# ProProject_dc_to_dc_2024-05-25.net
KiCad netlist of a schematic drawn in EasyEDA Pro
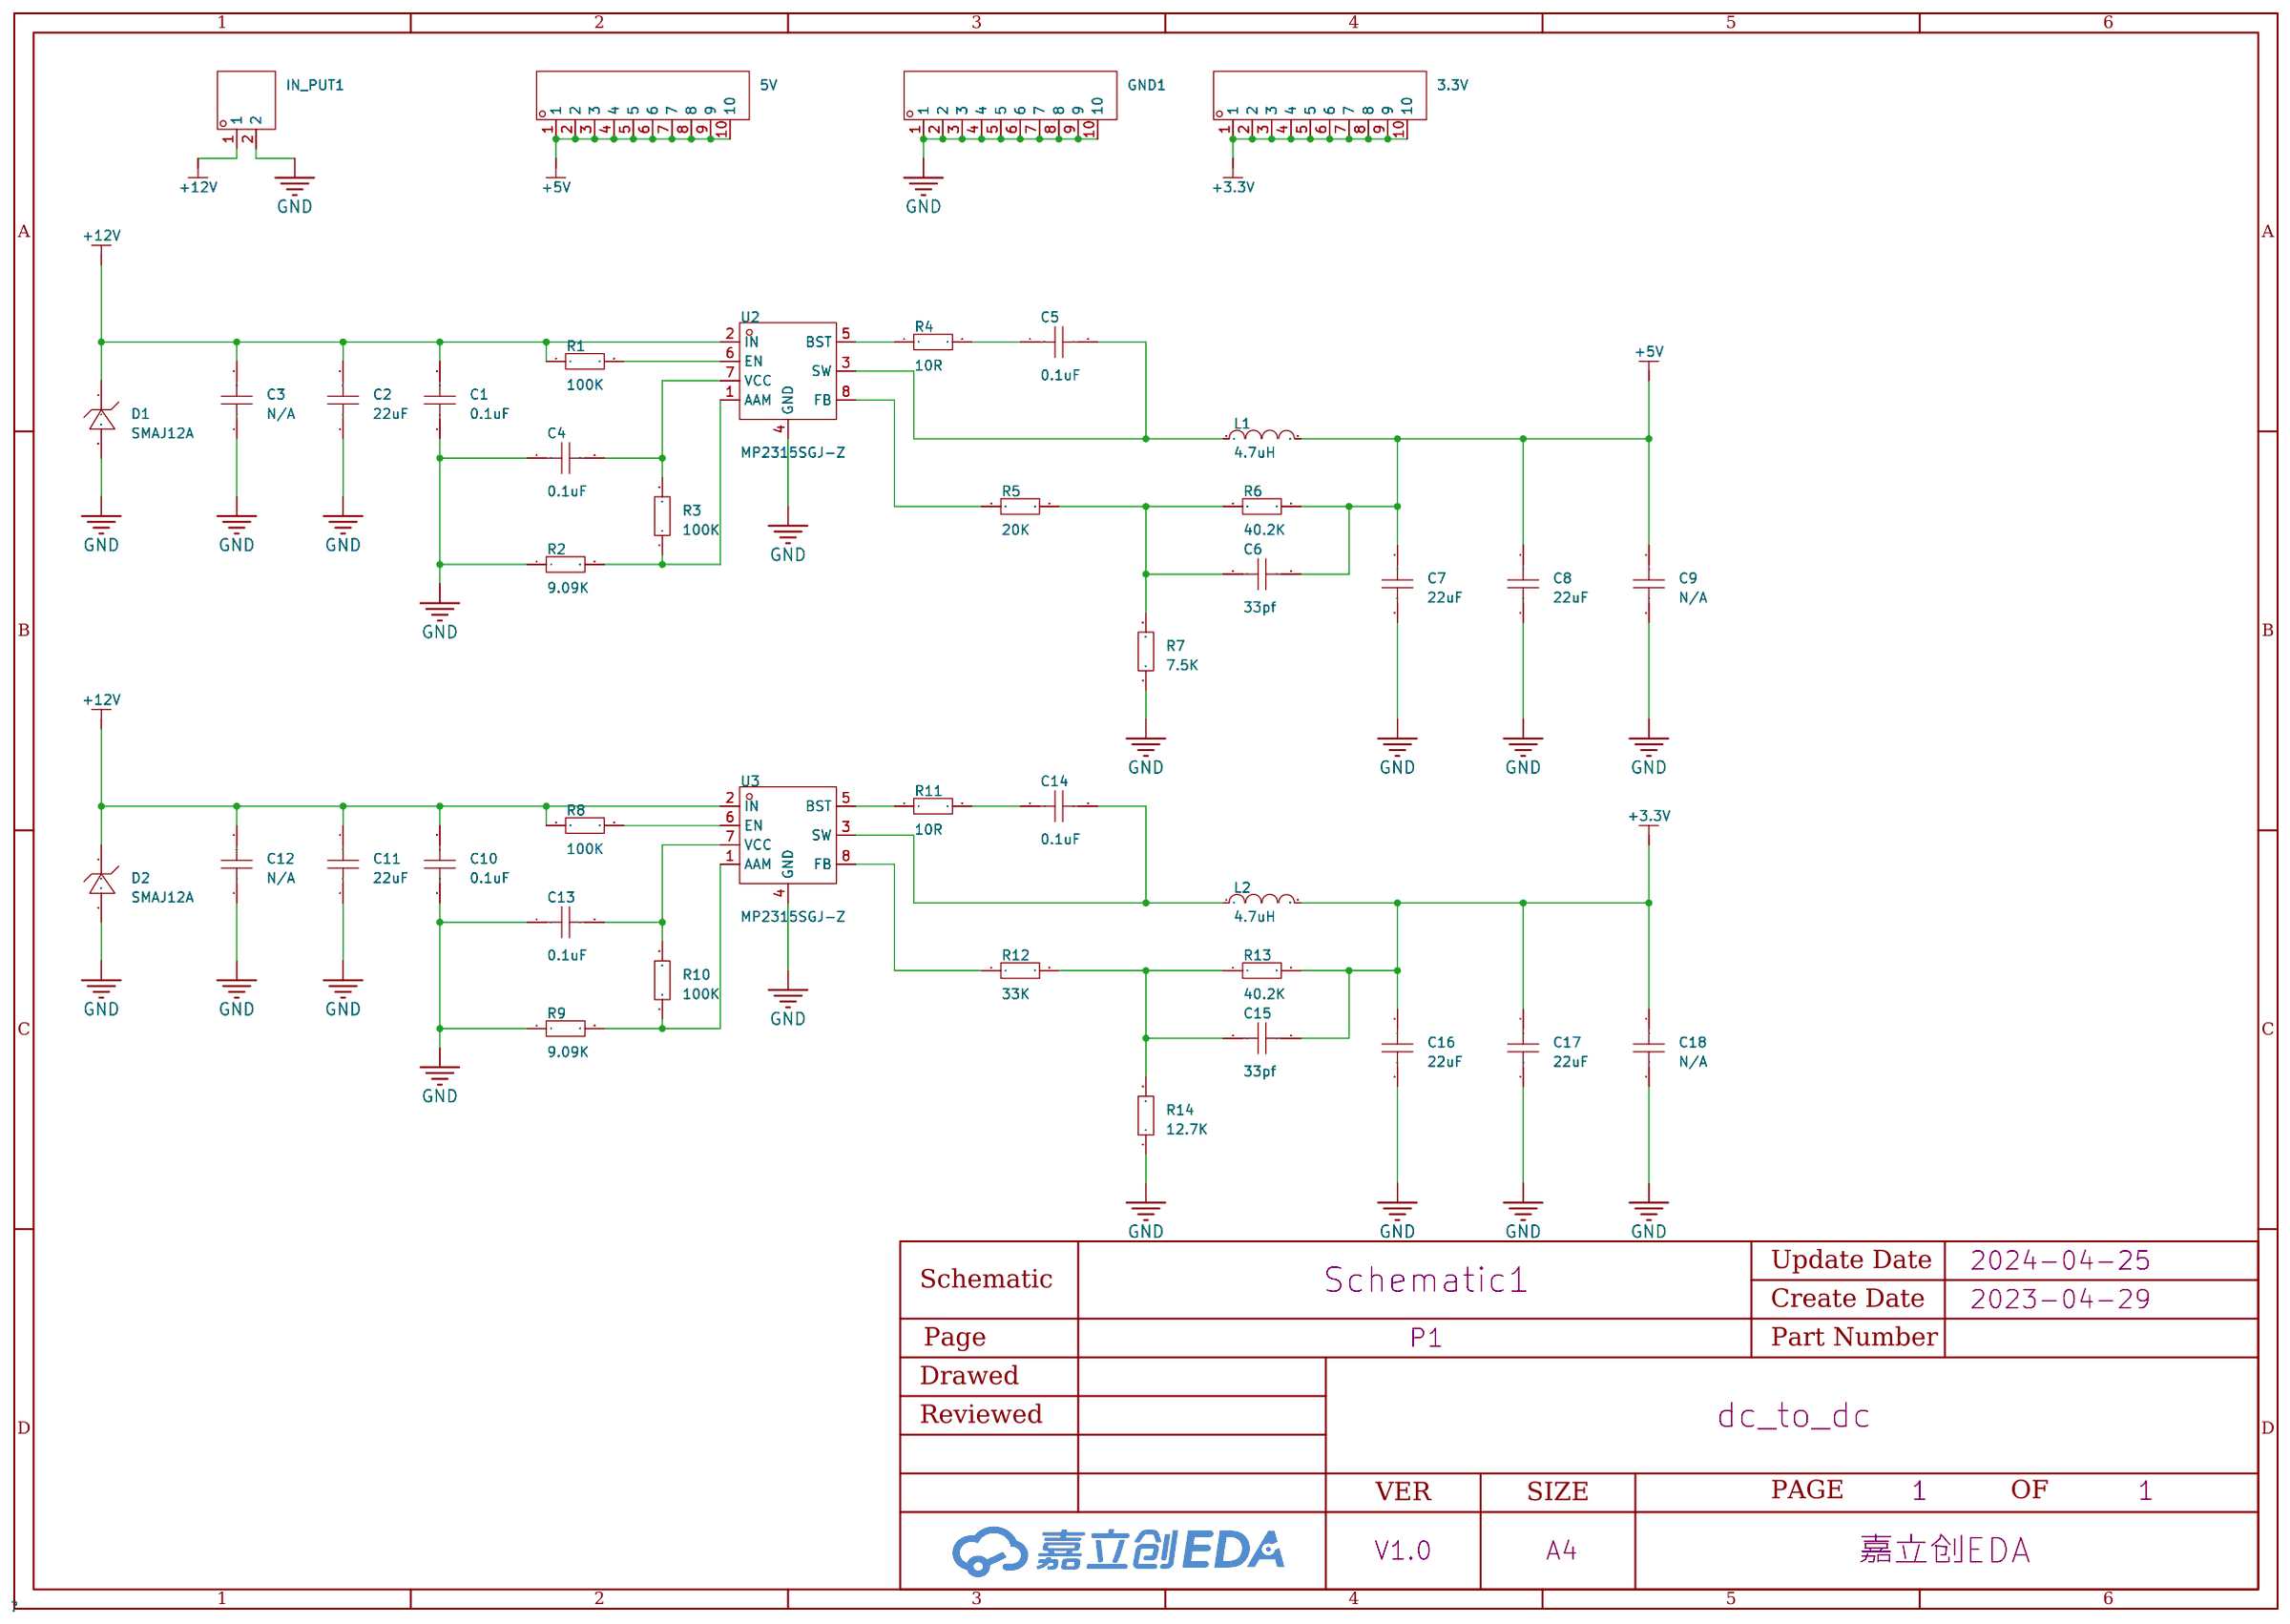
[diagram p0: schematic sheet]

(export (version "E")
  (design (tool "Eeschema 10.0.6"))
  (components
    (comp (ref "3.3V")
      (value "~")
      (footprint "easyedapro:HDR-TH_10P-P2.54-V-M-1")
      (libsource (lib "easyedapro") (part "Header-Male-2.54_1x10"))
    )
    (comp (ref "5V")
      (value "~")
      (footprint "easyedapro:HDR-TH_10P-P2.54-V-M-1")
      (libsource (lib "easyedapro") (part "Header-Male-2.54_1x10"))
    )
    (comp (ref "C1")
      (value "0.1uF")
      (footprint "easyedapro:C0603")
      (libsource (lib "easyedapro") (part "CapAcitance"))
    )
    (comp (ref "C2")
      (value "22uF")
      (footprint "easyedapro:C0603")
      (libsource (lib "easyedapro") (part "CapAcitance"))
    )
    (comp (ref "C3")
      (value "N/A")
      (footprint "easyedapro:C0603")
      (libsource (lib "easyedapro") (part "CapAcitance"))
    )
    (comp (ref "C4")
      (value "0.1uF")
      (footprint "easyedapro:C0603")
      (libsource (lib "easyedapro") (part "CapAcitance"))
    )
    (comp (ref "C5")
      (value "0.1uF")
      (footprint "easyedapro:C0603")
      (libsource (lib "easyedapro") (part "CapAcitance"))
    )
    (comp (ref "C6")
      (value "33pf")
      (footprint "easyedapro:C0603")
      (libsource (lib "easyedapro") (part "CapAcitance"))
    )
    (comp (ref "C7")
      (value "22uF")
      (footprint "easyedapro:C0603")
      (libsource (lib "easyedapro") (part "CapAcitance"))
    )
    (comp (ref "C8")
      (value "22uF")
      (footprint "easyedapro:C0603")
      (libsource (lib "easyedapro") (part "CapAcitance"))
    )
    (comp (ref "C9")
      (value "N/A")
      (footprint "easyedapro:C0603")
      (libsource (lib "easyedapro") (part "CapAcitance"))
    )
    (comp (ref "C10")
      (value "0.1uF")
      (footprint "easyedapro:C0603")
      (libsource (lib "easyedapro") (part "CapAcitance"))
    )
    (comp (ref "C11")
      (value "22uF")
      (footprint "easyedapro:C0603")
      (libsource (lib "easyedapro") (part "CapAcitance"))
    )
    (comp (ref "C12")
      (value "N/A")
      (footprint "easyedapro:C0603")
      (libsource (lib "easyedapro") (part "CapAcitance"))
    )
    (comp (ref "C13")
      (value "0.1uF")
      (footprint "easyedapro:C0603")
      (libsource (lib "easyedapro") (part "CapAcitance"))
    )
    (comp (ref "C14")
      (value "0.1uF")
      (footprint "easyedapro:C0603")
      (libsource (lib "easyedapro") (part "CapAcitance"))
    )
    (comp (ref "C15")
      (value "33pf")
      (footprint "easyedapro:C0603")
      (libsource (lib "easyedapro") (part "CapAcitance"))
    )
    (comp (ref "C16")
      (value "22uF")
      (footprint "easyedapro:C0603")
      (libsource (lib "easyedapro") (part "CapAcitance"))
    )
    (comp (ref "C17")
      (value "22uF")
      (footprint "easyedapro:C0603")
      (libsource (lib "easyedapro") (part "CapAcitance"))
    )
    (comp (ref "C18")
      (value "N/A")
      (footprint "easyedapro:C0603")
      (libsource (lib "easyedapro") (part "CapAcitance"))
    )
    (comp (ref "D1")
      (value "SMAJ12A")
      (footprint "easyedapro:SMA_L4.4-W2.8-LS5.4-RD")
      (description "极性:Unidirectional;峰值脉冲电流（10/1000us）:20.1A;箝位电压:19.9V;击穿电压（最小值）:13.3V;反向关断电压（典型值）:12V;")
      (libsource (lib "easyedapro") (part "SMAJ12A_C220440"))
    )
    (comp (ref "D2")
      (value "SMAJ12A")
      (footprint "easyedapro:SMA_L4.4-W2.8-LS5.4-RD")
      (description "极性:Unidirectional;峰值脉冲电流（10/1000us）:20.1A;箝位电压:19.9V;击穿电压（最小值）:13.3V;反向关断电压（典型值）:12V;")
      (libsource (lib "easyedapro") (part "SMAJ12A_C220440"))
    )
    (comp (ref "GND1")
      (value "~")
      (footprint "easyedapro:HDR-TH_10P-P2.54-V-M-1")
      (libsource (lib "easyedapro") (part "Header-Male-2.54_1x10"))
    )
    (comp (ref "IN_PUT1")
      (value "~")
      (footprint "easyedapro:HDR-TH_2P-P2.54-V-M-1")
      (libsource (lib "easyedapro") (part "210S-1*2P L=11.6MMGold-plated black"))
    )
    (comp (ref "L1")
      (value "4.7uH")
      (footprint "easyedapro:IND-SMD_L7.3-W6.6_MHCI06030")
      (description "电感值:4.7uH;精度:±20%;额定电流:5.5A;饱和电流(Isat):9A;")
      (fields
        (field (name "Manufacturer Part") "MHCI06030-4R7M-R8")
        (field (name "Manufacturer") "chilisin(奇力新)")
      )
      (libsource (lib "easyedapro") (part "MHCI06030-4R7M-R8"))
    )
    (comp (ref "L2")
      (value "4.7uH")
      (footprint "easyedapro:IND-SMD_L7.3-W6.6_MHCI06030")
      (description "电感值:4.7uH;精度:±20%;额定电流:5.5A;饱和电流(Isat):9A;")
      (fields
        (field (name "Manufacturer Part") "MHCI06030-4R7M-R8")
        (field (name "Manufacturer") "chilisin(奇力新)")
      )
      (libsource (lib "easyedapro") (part "MHCI06030-4R7M-R8"))
    )
    (comp (ref "R1") (value "100K") (footprint "easyedapro:R0603") (libsource (lib "easyedapro") (part "电阻")))
    (comp (ref "R2")
      (value "9.09K")
      (footprint "easyedapro:R0603")
      (libsource (lib "easyedapro") (part "电阻"))
    )
    (comp (ref "R3") (value "100K") (footprint "easyedapro:R0603") (libsource (lib "easyedapro") (part "电阻")))
    (comp (ref "R4") (value "10R") (footprint "easyedapro:R0603") (libsource (lib "easyedapro") (part "电阻")))
    (comp (ref "R5") (value "20K") (footprint "easyedapro:R0603") (libsource (lib "easyedapro") (part "电阻")))
    (comp (ref "R6")
      (value "40.2K")
      (footprint "easyedapro:R0603")
      (libsource (lib "easyedapro") (part "电阻"))
    )
    (comp (ref "R7") (value "7.5K") (footprint "easyedapro:R0603") (libsource (lib "easyedapro") (part "电阻")))
    (comp (ref "R8") (value "100K") (footprint "easyedapro:R0603") (libsource (lib "easyedapro") (part "电阻")))
    (comp (ref "R9")
      (value "9.09K")
      (footprint "easyedapro:R0603")
      (libsource (lib "easyedapro") (part "电阻"))
    )
    (comp (ref "R10")
      (value "100K")
      (footprint "easyedapro:R0603")
      (libsource (lib "easyedapro") (part "电阻"))
    )
    (comp (ref "R11") (value "10R") (footprint "easyedapro:R0603") (libsource (lib "easyedapro") (part "电阻")))
    (comp (ref "R12") (value "33K") (footprint "easyedapro:R0603") (libsource (lib "easyedapro") (part "电阻")))
    (comp (ref "R13")
      (value "40.2K")
      (footprint "easyedapro:R0603")
      (libsource (lib "easyedapro") (part "电阻"))
    )
    (comp (ref "R14")
      (value "12.7K")
      (footprint "easyedapro:R0603")
      (libsource (lib "easyedapro") (part "电阻"))
    )
    (comp (ref "U2")
      (value "MP2315SGJ-Z")
      (footprint "easyedapro:TSOT-23-8_L2.9-W1.6-P0.65-LS2.8-BL")
      (libsource (lib "easyedapro") (part "MP2315SGJ-Z"))
    )
    (comp (ref "U3")
      (value "MP2315SGJ-Z")
      (footprint "easyedapro:TSOT-23-8_L2.9-W1.6-P0.65-LS2.8-BL")
      (libsource (lib "easyedapro") (part "MP2315SGJ-Z"))
    )
  )
  (nets
    (net (code "1") (name "+3.3V") (class "Default")
      (node (ref "3.3V") (pin "1") (pinfunction "1_1") (pintype "input"))
      (node (ref "3.3V") (pin "10") (pinfunction "10_10") (pintype "input"))
      (node (ref "3.3V") (pin "2") (pinfunction "2_2") (pintype "input"))
      (node (ref "3.3V") (pin "3") (pinfunction "3_3") (pintype "input"))
      (node (ref "3.3V") (pin "4") (pinfunction "4_4") (pintype "input"))
      (node (ref "3.3V") (pin "5") (pinfunction "5_5") (pintype "input"))
      (node (ref "3.3V") (pin "6") (pinfunction "6_6") (pintype "input"))
      (node (ref "3.3V") (pin "7") (pinfunction "7_7") (pintype "input"))
      (node (ref "3.3V") (pin "8") (pinfunction "8_8") (pintype "input"))
      (node (ref "3.3V") (pin "9") (pinfunction "9_9") (pintype "input"))
      (node (ref "C15") (pin "2") (pinfunction "2_2") (pintype "input"))
      (node (ref "C16") (pin "1") (pinfunction "1_1") (pintype "input"))
      (node (ref "C17") (pin "1") (pinfunction "1_1") (pintype "input"))
      (node (ref "C18") (pin "1") (pinfunction "1_1") (pintype "input"))
      (node (ref "L2") (pin "2") (pinfunction "2_2") (pintype "input"))
      (node (ref "R13") (pin "2") (pinfunction "2_2") (pintype "input"))
    )
    (net (code "2") (name "+5V") (class "Default")
      (node (ref "5V") (pin "1") (pinfunction "1_1") (pintype "input"))
      (node (ref "5V") (pin "10") (pinfunction "10_10") (pintype "input"))
      (node (ref "5V") (pin "2") (pinfunction "2_2") (pintype "input"))
      (node (ref "5V") (pin "3") (pinfunction "3_3") (pintype "input"))
      (node (ref "5V") (pin "4") (pinfunction "4_4") (pintype "input"))
      (node (ref "5V") (pin "5") (pinfunction "5_5") (pintype "input"))
      (node (ref "5V") (pin "6") (pinfunction "6_6") (pintype "input"))
      (node (ref "5V") (pin "7") (pinfunction "7_7") (pintype "input"))
      (node (ref "5V") (pin "8") (pinfunction "8_8") (pintype "input"))
      (node (ref "5V") (pin "9") (pinfunction "9_9") (pintype "input"))
      (node (ref "C6") (pin "2") (pinfunction "2_2") (pintype "input"))
      (node (ref "C7") (pin "1") (pinfunction "1_1") (pintype "input"))
      (node (ref "C8") (pin "1") (pinfunction "1_1") (pintype "input"))
      (node (ref "C9") (pin "1") (pinfunction "1_1") (pintype "input"))
      (node (ref "L1") (pin "2") (pinfunction "2_2") (pintype "input"))
      (node (ref "R6") (pin "2") (pinfunction "2_2") (pintype "input"))
    )
    (net (code "3") (name "+12V") (class "Default")
      (node (ref "C1") (pin "2") (pinfunction "2_2") (pintype "input"))
      (node (ref "C10") (pin "2") (pinfunction "2_2") (pintype "input"))
      (node (ref "C11") (pin "2") (pinfunction "2_2") (pintype "input"))
      (node (ref "C12") (pin "2") (pinfunction "2_2") (pintype "input"))
      (node (ref "C2") (pin "2") (pinfunction "2_2") (pintype "input"))
      (node (ref "C3") (pin "2") (pinfunction "2_2") (pintype "input"))
      (node (ref "D1") (pin "1") (pinfunction "1_1") (pintype "input"))
      (node (ref "D2") (pin "1") (pinfunction "1_1") (pintype "input"))
      (node (ref "IN_PUT1") (pin "1") (pinfunction "1_1") (pintype "input"))
      (node (ref "R1") (pin "1") (pinfunction "1_1") (pintype "input"))
      (node (ref "R8") (pin "1") (pinfunction "1_1") (pintype "input"))
      (node (ref "U2") (pin "2") (pinfunction "IN_2") (pintype "input"))
      (node (ref "U3") (pin "2") (pinfunction "IN_2") (pintype "input"))
    )
    (net (code "4") (name "GND") (class "Default")
      (node (ref "C1") (pin "1") (pinfunction "1_1") (pintype "input"))
      (node (ref "C10") (pin "1") (pinfunction "1_1") (pintype "input"))
      (node (ref "C11") (pin "1") (pinfunction "1_1") (pintype "input"))
      (node (ref "C12") (pin "1") (pinfunction "1_1") (pintype "input"))
      (node (ref "C13") (pin "1") (pinfunction "1_1") (pintype "input"))
      (node (ref "C16") (pin "2") (pinfunction "2_2") (pintype "input"))
      (node (ref "C17") (pin "2") (pinfunction "2_2") (pintype "input"))
      (node (ref "C18") (pin "2") (pinfunction "2_2") (pintype "input"))
      (node (ref "C2") (pin "1") (pinfunction "1_1") (pintype "input"))
      (node (ref "C3") (pin "1") (pinfunction "1_1") (pintype "input"))
      (node (ref "C4") (pin "1") (pinfunction "1_1") (pintype "input"))
      (node (ref "C7") (pin "2") (pinfunction "2_2") (pintype "input"))
      (node (ref "C8") (pin "2") (pinfunction "2_2") (pintype "input"))
      (node (ref "C9") (pin "2") (pinfunction "2_2") (pintype "input"))
      (node (ref "D1") (pin "2") (pinfunction "2_2") (pintype "input"))
      (node (ref "D2") (pin "2") (pinfunction "2_2") (pintype "input"))
      (node (ref "GND1") (pin "1") (pinfunction "1_1") (pintype "input"))
      (node (ref "GND1") (pin "10") (pinfunction "10_10") (pintype "input"))
      (node (ref "GND1") (pin "2") (pinfunction "2_2") (pintype "input"))
      (node (ref "GND1") (pin "3") (pinfunction "3_3") (pintype "input"))
      (node (ref "GND1") (pin "4") (pinfunction "4_4") (pintype "input"))
      (node (ref "GND1") (pin "5") (pinfunction "5_5") (pintype "input"))
      (node (ref "GND1") (pin "6") (pinfunction "6_6") (pintype "input"))
      (node (ref "GND1") (pin "7") (pinfunction "7_7") (pintype "input"))
      (node (ref "GND1") (pin "8") (pinfunction "8_8") (pintype "input"))
      (node (ref "GND1") (pin "9") (pinfunction "9_9") (pintype "input"))
      (node (ref "IN_PUT1") (pin "2") (pinfunction "2_2") (pintype "input"))
      (node (ref "R14") (pin "1") (pinfunction "1_1") (pintype "input"))
      (node (ref "R2") (pin "1") (pinfunction "1_1") (pintype "input"))
      (node (ref "R7") (pin "1") (pinfunction "1_1") (pintype "input"))
      (node (ref "R9") (pin "1") (pinfunction "1_1") (pintype "input"))
      (node (ref "U2") (pin "4") (pinfunction "GND_4") (pintype "input"))
      (node (ref "U3") (pin "4") (pinfunction "GND_4") (pintype "input"))
    )
    (net (code "5") (name "Net-(C5-Pad1)") (class "Default")
      (node (ref "C5") (pin "1") (pinfunction "1_1") (pintype "input"))
      (node (ref "R4") (pin "2") (pinfunction "2_2") (pintype "input"))
    )
    (net (code "6") (name "Net-(C6-Pad1)") (class "Default")
      (node (ref "C6") (pin "1") (pinfunction "1_1") (pintype "input"))
      (node (ref "R5") (pin "2") (pinfunction "2_2") (pintype "input"))
      (node (ref "R6") (pin "1") (pinfunction "1_1") (pintype "input"))
      (node (ref "R7") (pin "2") (pinfunction "2_2") (pintype "input"))
    )
    (net (code "7") (name "Net-(C14-Pad1)") (class "Default")
      (node (ref "C14") (pin "1") (pinfunction "1_1") (pintype "input"))
      (node (ref "R11") (pin "2") (pinfunction "2_2") (pintype "input"))
    )
    (net (code "8") (name "Net-(C15-Pad1)") (class "Default")
      (node (ref "C15") (pin "1") (pinfunction "1_1") (pintype "input"))
      (node (ref "R12") (pin "2") (pinfunction "2_2") (pintype "input"))
      (node (ref "R13") (pin "1") (pinfunction "1_1") (pintype "input"))
      (node (ref "R14") (pin "2") (pinfunction "2_2") (pintype "input"))
    )
    (net (code "9") (name "Net-(U2-AAM)") (class "Default")
      (node (ref "R2") (pin "2") (pinfunction "2_2") (pintype "input"))
      (node (ref "R3") (pin "1") (pinfunction "1_1") (pintype "input"))
      (node (ref "U2") (pin "1") (pinfunction "AAM_1") (pintype "input"))
    )
    (net (code "10") (name "Net-(U2-BST)") (class "Default")
      (node (ref "R4") (pin "1") (pinfunction "1_1") (pintype "input"))
      (node (ref "U2") (pin "5") (pinfunction "BST_5") (pintype "input"))
    )
    (net (code "11") (name "Net-(U2-EN)") (class "Default")
      (node (ref "R1") (pin "2") (pinfunction "2_2") (pintype "input"))
      (node (ref "U2") (pin "6") (pinfunction "EN_6") (pintype "input"))
    )
    (net (code "12") (name "Net-(U2-FB)") (class "Default")
      (node (ref "R5") (pin "1") (pinfunction "1_1") (pintype "input"))
      (node (ref "U2") (pin "8") (pinfunction "FB_8") (pintype "input"))
    )
    (net (code "13") (name "Net-(U2-SW)") (class "Default")
      (node (ref "C5") (pin "2") (pinfunction "2_2") (pintype "input"))
      (node (ref "L1") (pin "1") (pinfunction "1_1") (pintype "input"))
      (node (ref "U2") (pin "3") (pinfunction "SW_3") (pintype "input"))
    )
    (net (code "14") (name "Net-(U2-VCC)") (class "Default")
      (node (ref "C4") (pin "2") (pinfunction "2_2") (pintype "input"))
      (node (ref "R3") (pin "2") (pinfunction "2_2") (pintype "input"))
      (node (ref "U2") (pin "7") (pinfunction "VCC_7") (pintype "input"))
    )
    (net (code "15") (name "Net-(U3-AAM)") (class "Default")
      (node (ref "R10") (pin "1") (pinfunction "1_1") (pintype "input"))
      (node (ref "R9") (pin "2") (pinfunction "2_2") (pintype "input"))
      (node (ref "U3") (pin "1") (pinfunction "AAM_1") (pintype "input"))
    )
    (net (code "16") (name "Net-(U3-BST)") (class "Default")
      (node (ref "R11") (pin "1") (pinfunction "1_1") (pintype "input"))
      (node (ref "U3") (pin "5") (pinfunction "BST_5") (pintype "input"))
    )
    (net (code "17") (name "Net-(U3-EN)") (class "Default")
      (node (ref "R8") (pin "2") (pinfunction "2_2") (pintype "input"))
      (node (ref "U3") (pin "6") (pinfunction "EN_6") (pintype "input"))
    )
    (net (code "18") (name "Net-(U3-FB)") (class "Default")
      (node (ref "R12") (pin "1") (pinfunction "1_1") (pintype "input"))
      (node (ref "U3") (pin "8") (pinfunction "FB_8") (pintype "input"))
    )
    (net (code "19") (name "Net-(U3-SW)") (class "Default")
      (node (ref "C14") (pin "2") (pinfunction "2_2") (pintype "input"))
      (node (ref "L2") (pin "1") (pinfunction "1_1") (pintype "input"))
      (node (ref "U3") (pin "3") (pinfunction "SW_3") (pintype "input"))
    )
    (net (code "20") (name "Net-(U3-VCC)") (class "Default")
      (node (ref "C13") (pin "2") (pinfunction "2_2") (pintype "input"))
      (node (ref "R10") (pin "2") (pinfunction "2_2") (pintype "input"))
      (node (ref "U3") (pin "7") (pinfunction "VCC_7") (pintype "input"))
    )
  )
)
